# Sensor.net
KiCad netlist of a schematic drawn in Altium Designer
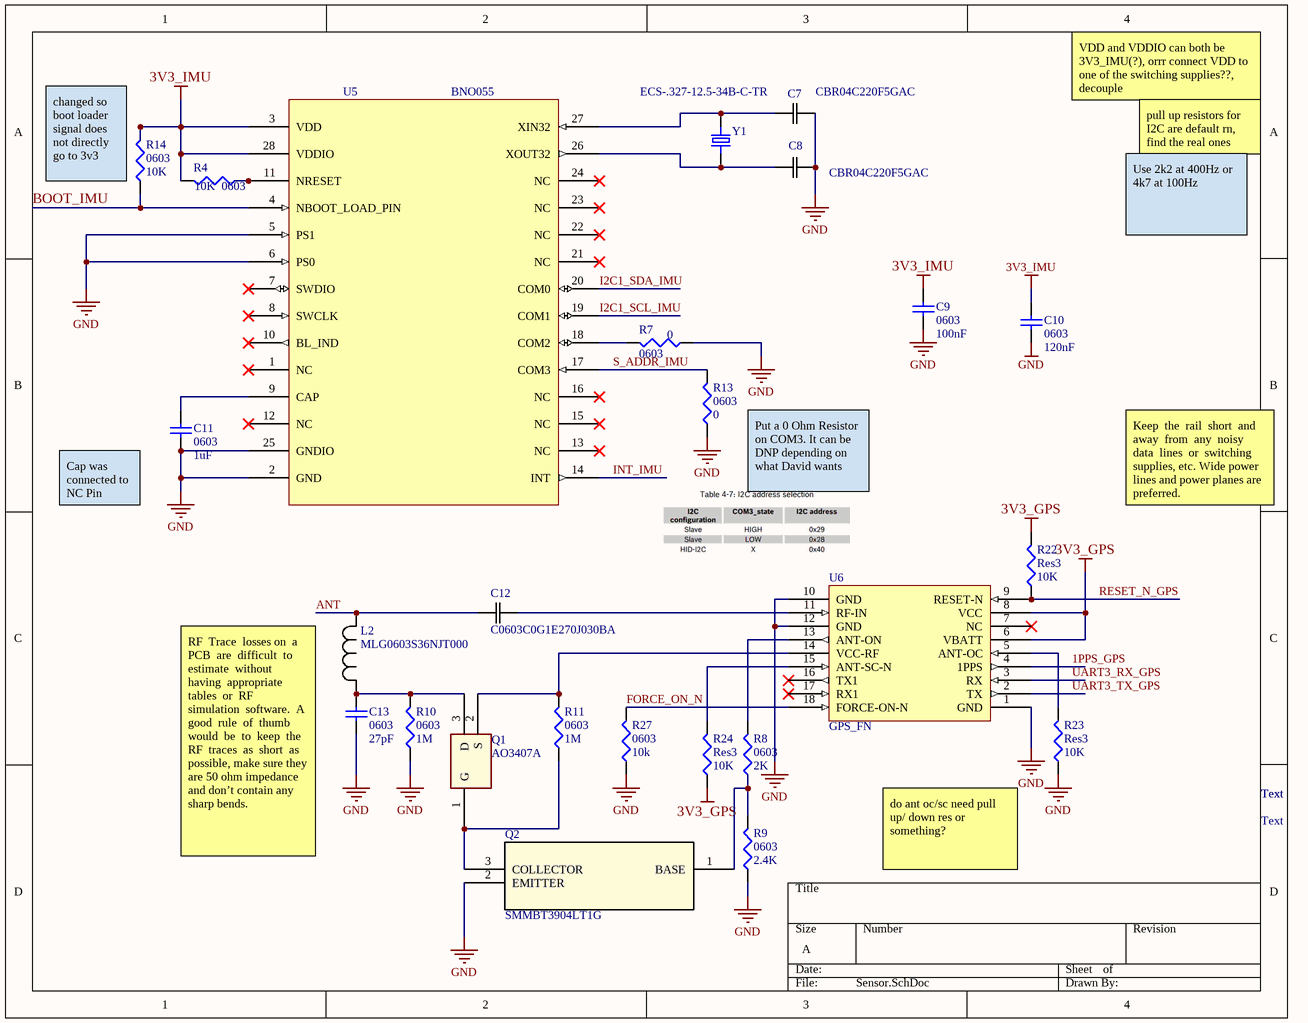
[diagram p0: Sensor.SchDoc]

(export (version "E")
  (design (tool "Eeschema 10.0.6"))
  (components
    (comp (ref "C7")
      (value "CBR04C220F5GAC")
      (footprint "swarm_crawler_pcb:CAPC10555_55N_KEM")
      (description "No Description Available")
      (fields (field (name "COPYRIGHT") "Copyright (C) 2023 Ultra Librarian. All rights reserved."))
      (libsource (lib "swarm_crawler_sch") (part "CBR04C220F5GAC"))
    )
    (comp (ref "C8")
      (value "CBR04C220F5GAC")
      (footprint "swarm_crawler_pcb:CAPC10555_55N_KEM")
      (description "No Description Available")
      (fields (field (name "COPYRIGHT") "Copyright (C) 2023 Ultra Librarian. All rights reserved."))
      (libsource (lib "swarm_crawler_sch") (part "CBR04C220F5GAC"))
    )
    (comp (ref "C9")
      (value "0603")
      (footprint "1608[0603]")
      (description "Capacitor (Semiconductor SIM Model)")
      (fields (field (name "ALTIUM_VALUE") "100nF") (field (name "PUBLISHER") "Altium Limited"))
      (libsource (lib "Miscellaneous Devices") (part "Cap Semi"))
    )
    (comp (ref "C10")
      (value "0603")
      (footprint "1608[0603]")
      (description "Capacitor (Semiconductor SIM Model)")
      (fields (field (name "ALTIUM_VALUE") "120nF") (field (name "PUBLISHER") "Altium Limited"))
      (libsource (lib "Miscellaneous Devices") (part "Cap Semi"))
    )
    (comp (ref "C11")
      (value "0603")
      (footprint "1608[0603]")
      (description "Capacitor (Semiconductor SIM Model)")
      (fields (field (name "ALTIUM_VALUE") "1uF") (field (name "PUBLISHER") "Altium Limited"))
      (libsource (lib "Miscellaneous Devices") (part "Cap Semi"))
    )
    (comp (ref "C12")
      (value "C0603C0G1E270J030BA")
      (footprint "swarm_crawler_pcb:CAP_0603_TDK")
      (description "No Description Available")
      (fields (field (name "COPYRIGHT") "Copyright (C) 2023 Ultra Librarian. All rights reserved."))
      (libsource (lib "swarm_crawler_sch") (part "C0603C0G1E270J030BA"))
    )
    (comp (ref "C13")
      (value "0603")
      (footprint "1608[0603]")
      (description "Capacitor (Semiconductor SIM Model)")
      (fields (field (name "ALTIUM_VALUE") "27pF") (field (name "PUBLISHER") "Altium Limited"))
      (libsource (lib "Miscellaneous Devices") (part "Cap Semi"))
    )
    (comp (ref "L2")
      (value "MLG0603S36NJT000")
      (footprint "swarm_crawler_pcb:IND_0603_TDK")
      (description "No Description Available")
      (fields (field (name "COPYRIGHT") "Copyright (C) 2023 Ultra Librarian. All rights reserved."))
      (libsource (lib "swarm_crawler_sch") (part "MLG0603S36NJT000"))
    )
    (comp (ref "Q1")
      (value "AO3407A")
      (footprint "swarm_crawler_pcb:SOT-23-3L_AOS")
      (description "No Description Available")
      (fields (field (name "COPYRIGHT") "Copyright (C) 2023 Ultra Librarian. All rights reserved."))
      (libsource (lib "swarm_crawler_sch") (part "AO3407A"))
    )
    (comp (ref "Q2")
      (value "SMMBT3904LT1G")
      (footprint "swarm_crawler_pcb:SOT-23-3_1P4X3P040_ONS")
      (description "No Description Available")
      (fields (field (name "COPYRIGHT") "Copyright (C) 2023 Ultra Librarian. All rights reserved."))
      (libsource (lib "swarm_crawler_sch") (part "SMMBT3904LT1G"))
    )
    (comp (ref "R4")
      (value "0603")
      (footprint "J1-0603")
      (description "Resistor")
      (fields (field (name "ALTIUM_VALUE") "10K") (field (name "PUBLISHER") "Altium Limited"))
      (libsource (lib "Miscellaneous Devices") (part "Res3"))
    )
    (comp (ref "R7")
      (value "0603")
      (footprint "J1-0603")
      (description "Resistor")
      (fields (field (name "ALTIUM_VALUE") "0") (field (name "PUBLISHER") "Altium Limited"))
      (libsource (lib "Miscellaneous Devices") (part "Res3"))
    )
    (comp (ref "R8")
      (value "0603")
      (footprint "J1-0603")
      (description "Resistor")
      (fields (field (name "ALTIUM_VALUE") "2K") (field (name "PUBLISHER") "Altium Limited"))
      (libsource (lib "Miscellaneous Devices") (part "Res3"))
    )
    (comp (ref "R9")
      (value "0603")
      (footprint "J1-0603")
      (description "Resistor")
      (fields (field (name "ALTIUM_VALUE") "2.4K") (field (name "PUBLISHER") "Altium Limited"))
      (libsource (lib "Miscellaneous Devices") (part "Res3"))
    )
    (comp (ref "R10")
      (value "0603")
      (footprint "J1-0603")
      (description "Resistor")
      (fields (field (name "ALTIUM_VALUE") "1M") (field (name "PUBLISHER") "Altium Limited"))
      (libsource (lib "Miscellaneous Devices") (part "Res3"))
    )
    (comp (ref "R11")
      (value "0603")
      (footprint "J1-0603")
      (description "Resistor")
      (fields (field (name "ALTIUM_VALUE") "1M") (field (name "PUBLISHER") "Altium Limited"))
      (libsource (lib "Miscellaneous Devices") (part "Res3"))
    )
    (comp (ref "R13")
      (value "0603")
      (footprint "J1-0603")
      (description "Resistor")
      (fields (field (name "ALTIUM_VALUE") "0") (field (name "PUBLISHER") "Altium Limited"))
      (libsource (lib "Miscellaneous Devices") (part "Res3"))
    )
    (comp (ref "R14")
      (value "0603")
      (footprint "J1-0603")
      (description "Resistor")
      (fields (field (name "ALTIUM_VALUE") "10K") (field (name "PUBLISHER") "Altium Limited"))
      (libsource (lib "Miscellaneous Devices") (part "Res3"))
    )
    (comp (ref "R22")
      (value "Res3")
      (footprint "J1-0603")
      (description "Resistor")
      (fields (field (name "ALTIUM_VALUE") "10K") (field (name "PUBLISHER") "Altium Limited"))
      (libsource (lib "Miscellaneous Devices") (part "Res3"))
    )
    (comp (ref "R23")
      (value "Res3")
      (footprint "J1-0603")
      (description "Resistor")
      (fields (field (name "ALTIUM_VALUE") "10K") (field (name "PUBLISHER") "Altium Limited"))
      (libsource (lib "Miscellaneous Devices") (part "Res3"))
    )
    (comp (ref "R24")
      (value "Res3")
      (footprint "J1-0603")
      (description "Resistor")
      (fields (field (name "ALTIUM_VALUE") "10K") (field (name "PUBLISHER") "Altium Limited"))
      (libsource (lib "Miscellaneous Devices") (part "Res3"))
    )
    (comp (ref "R27")
      (value "0603")
      (footprint "J1-0603")
      (description "Resistor")
      (fields (field (name "ALTIUM_VALUE") "10k") (field (name "PUBLISHER") "Altium Limited"))
      (libsource (lib "Miscellaneous Devices") (part "Res3"))
    )
    (comp (ref "U5")
      (value "BNO055")
      (footprint "swarm_crawler_pcb:QFN_BNO055_BOS")
      (description "No Description Available")
      (fields (field (name "COPYRIGHT") "Copyright (C) 2023 Ultra Librarian. All rights reserved."))
      (libsource (lib "swarm_crawler_sch") (part "BNO055"))
    )
    (comp (ref "U6")
      (value "GPS_FN")
      (footprint "swarm_crawler_pcb:SL871")
      (libsource (lib "swarm_crawler_sch") (part "GPS_FN"))
    )
    (comp (ref "Y1")
      (value "ECS-.327-12.5-34B-C-TR")
      (footprint "swarm_crawler_pcb:XTAL_ECS-.327-12.5-34B-C-TR")
      (description "32.768kHz Â±10ppm Crystal 12.5pF 70 kOhms 2-SMD, No Lead")
      (fields (field (name "DIGI-KEY_PART_NUMBER") "XC1968CT-ND") (field (name "MF") "ECS Inc."))
      (libsource (lib "swarm_crawler_sch") (part "ECS-.327-12.5-34B-C-TR"))
    )
  )
  (nets
    (net (code "1") (name "/1PPS_GPS") (class "Default")
      (node (ref "U6") (pin "4") (pinfunction "1PPS_4") (pintype "output"))
    )
    (net (code "2") (name "/ANT") (class "Default")
      (node (ref "C12") (pin "1") (pinfunction "1_1") (pintype "passive"))
      (node (ref "L2") (pin "1") (pinfunction "1_1") (pintype "passive"))
    )
    (net (code "3") (name "/BOOT_IMU") (class "Default")
      (node (ref "R14") (pin "1") (pinfunction "1_1") (pintype "passive"))
      (node (ref "U5") (pin "4") (pinfunction "NBOOT_LOAD_PIN_4") (pintype "input"))
    )
    (net (code "4") (name "/FORCE_ON_N") (class "Default")
      (node (ref "R27") (pin "2") (pinfunction "2_2") (pintype "passive"))
      (node (ref "U6") (pin "18") (pinfunction "FORCE-ON-N_18") (pintype "input"))
    )
    (net (code "5") (name "/I2C1_SCL_IMU") (class "Default")
      (node (ref "U5") (pin "19") (pinfunction "COM1_19") (pintype "bidirectional"))
    )
    (net (code "6") (name "/I2C1_SDA_IMU") (class "Default")
      (node (ref "U5") (pin "20") (pinfunction "COM0_20") (pintype "bidirectional"))
    )
    (net (code "7") (name "/INT_IMU") (class "Default")
      (node (ref "U5") (pin "14") (pinfunction "INT_14") (pintype "output"))
    )
    (net (code "8") (name "/RESET_N_GPS") (class "Default")
      (node (ref "R22") (pin "1") (pinfunction "1_1") (pintype "passive"))
      (node (ref "U6") (pin "9") (pinfunction "RESET-N_9") (pintype "input"))
    )
    (net (code "9") (name "/S_ADDR_IMU") (class "Default")
      (node (ref "R13") (pin "2") (pinfunction "2_2") (pintype "passive"))
      (node (ref "U5") (pin "17") (pinfunction "COM3_17") (pintype "input"))
    )
    (net (code "10") (name "/UART3_RX_GPS") (class "Default")
      (node (ref "U6") (pin "3") (pinfunction "RX_3") (pintype "input"))
    )
    (net (code "11") (name "/UART3_TX_GPS") (class "Default")
      (node (ref "U6") (pin "2") (pinfunction "TX_2") (pintype "output"))
    )
    (net (code "12") (name "3V3_GPS") (class "Default")
      (node (ref "R22") (pin "2") (pinfunction "2_2") (pintype "passive"))
      (node (ref "R24") (pin "1") (pinfunction "1_1") (pintype "passive"))
      (node (ref "U6") (pin "6") (pinfunction "VBATT_6") (pintype "power_in"))
      (node (ref "U6") (pin "8") (pinfunction "VCC_8") (pintype "power_in"))
    )
    (net (code "13") (name "3V3_IMU") (class "Default")
      (node (ref "C10") (pin "2") (pinfunction "2_2") (pintype "passive"))
      (node (ref "C9") (pin "2") (pinfunction "2_2") (pintype "passive"))
      (node (ref "R14") (pin "2") (pinfunction "2_2") (pintype "passive"))
      (node (ref "R4") (pin "2") (pinfunction "2_2") (pintype "passive"))
      (node (ref "U5") (pin "28") (pinfunction "VDDIO_28") (pintype "power_in"))
      (node (ref "U5") (pin "3") (pinfunction "VDD_3") (pintype "power_in"))
    )
    (net (code "14") (name "GND") (class "Default")
      (node (ref "C10") (pin "1") (pinfunction "1_1") (pintype "passive"))
      (node (ref "C11") (pin "1") (pinfunction "1_1") (pintype "passive"))
      (node (ref "C13") (pin "1") (pinfunction "1_1") (pintype "passive"))
      (node (ref "C7") (pin "2") (pinfunction "2_2") (pintype "passive"))
      (node (ref "C8") (pin "2") (pinfunction "2_2") (pintype "passive"))
      (node (ref "C9") (pin "1") (pinfunction "1_1") (pintype "passive"))
      (node (ref "Q2") (pin "2") (pinfunction "EMITTER_2") (pintype "passive"))
      (node (ref "R10") (pin "1") (pinfunction "1_1") (pintype "passive"))
      (node (ref "R13") (pin "1") (pinfunction "1_1") (pintype "passive"))
      (node (ref "R23") (pin "1") (pinfunction "1_1") (pintype "passive"))
      (node (ref "R27") (pin "1") (pinfunction "1_1") (pintype "passive"))
      (node (ref "R7") (pin "1") (pinfunction "1_1") (pintype "passive"))
      (node (ref "R9") (pin "1") (pinfunction "1_1") (pintype "passive"))
      (node (ref "U5") (pin "2") (pinfunction "GND_2") (pintype "passive"))
      (node (ref "U5") (pin "25") (pinfunction "GNDIO_25") (pintype "passive"))
      (node (ref "U5") (pin "5") (pinfunction "PS1_5") (pintype "input"))
      (node (ref "U5") (pin "6") (pinfunction "PS0_6") (pintype "input"))
      (node (ref "U6") (pin "1") (pinfunction "GND_1") (pintype "power_in"))
      (node (ref "U6") (pin "10") (pinfunction "GND_10") (pintype "power_in"))
      (node (ref "U6") (pin "12") (pinfunction "GND_12") (pintype "power_in"))
    )
    (net (code "15") (name "Net-(Q1-D)") (class "Default")
      (node (ref "C13") (pin "2") (pinfunction "2_2") (pintype "passive"))
      (node (ref "L2") (pin "2") (pinfunction "2_2") (pintype "passive"))
      (node (ref "Q1") (pin "3") (pinfunction "D_3") (pintype "passive"))
      (node (ref "R10") (pin "2") (pinfunction "2_2") (pintype "passive"))
    )
    (net (code "16") (name "Net-(Q1-G)") (class "Default")
      (node (ref "Q1") (pin "1") (pinfunction "G_1") (pintype "passive"))
      (node (ref "Q2") (pin "3") (pinfunction "COLLECTOR_3") (pintype "passive"))
      (node (ref "R11") (pin "1") (pinfunction "1_1") (pintype "passive"))
    )
    (net (code "17") (name "Net-(Q1-S)") (class "Default")
      (node (ref "Q1") (pin "2") (pinfunction "S_2") (pintype "passive"))
      (node (ref "R11") (pin "2") (pinfunction "2_2") (pintype "passive"))
      (node (ref "U6") (pin "14") (pinfunction "VCC-RF_14") (pintype "power_in"))
    )
    (net (code "18") (name "Net-(Q2-BASE)") (class "Default")
      (node (ref "Q2") (pin "1") (pinfunction "BASE_1") (pintype "passive"))
      (node (ref "R8") (pin "1") (pinfunction "1_1") (pintype "passive"))
      (node (ref "R9") (pin "2") (pinfunction "2_2") (pintype "passive"))
    )
    (net (code "19") (name "Net-(U5-CAP)") (class "Default")
      (node (ref "C11") (pin "2") (pinfunction "2_2") (pintype "passive"))
      (node (ref "U5") (pin "9") (pinfunction "CAP_9") (pintype "passive"))
    )
    (net (code "20") (name "Net-(U5-COM2)") (class "Default")
      (node (ref "R7") (pin "2") (pinfunction "2_2") (pintype "passive"))
      (node (ref "U5") (pin "18") (pinfunction "COM2_18") (pintype "bidirectional"))
    )
    (net (code "21") (name "Net-(U5-NRESET)") (class "Default")
      (node (ref "R4") (pin "1") (pinfunction "1_1") (pintype "passive"))
      (node (ref "U5") (pin "11") (pinfunction "NRESET_11") (pintype "passive"))
    )
    (net (code "22") (name "Net-(U5-XIN32)") (class "Default")
      (node (ref "C7") (pin "1") (pinfunction "1_1") (pintype "passive"))
      (node (ref "U5") (pin "27") (pinfunction "XIN32_27") (pintype "input"))
      (node (ref "Y1") (pin "2") (pinfunction "2_2") (pintype "passive"))
    )
    (net (code "23") (name "Net-(U5-XOUT32)") (class "Default")
      (node (ref "C8") (pin "1") (pinfunction "1_1") (pintype "passive"))
      (node (ref "U5") (pin "26") (pinfunction "XOUT32_26") (pintype "output"))
      (node (ref "Y1") (pin "1") (pinfunction "1_1") (pintype "passive"))
    )
    (net (code "24") (name "Net-(U6-ANT-OC)") (class "Default")
      (node (ref "R23") (pin "2") (pinfunction "2_2") (pintype "passive"))
      (node (ref "U6") (pin "5") (pinfunction "ANT-OC_5") (pintype "input"))
    )
    (net (code "25") (name "Net-(U6-ANT-ON)") (class "Default")
      (node (ref "R8") (pin "2") (pinfunction "2_2") (pintype "passive"))
      (node (ref "U6") (pin "13") (pinfunction "ANT-ON_13") (pintype "output"))
    )
    (net (code "26") (name "Net-(U6-ANT-SC-N)") (class "Default")
      (node (ref "R24") (pin "2") (pinfunction "2_2") (pintype "passive"))
      (node (ref "U6") (pin "15") (pinfunction "ANT-SC-N_15") (pintype "input"))
    )
    (net (code "27") (name "Net-(U6-RF-IN)") (class "Default")
      (node (ref "C12") (pin "2") (pinfunction "2_2") (pintype "passive"))
      (node (ref "U6") (pin "11") (pinfunction "RF-IN_11") (pintype "input"))
    )
    (net (code "28") (name "unconnected-(U5-BL_IND-Pad10)") (class "Default")
      (node (ref "U5") (pin "10") (pinfunction "BL_IND_10") (pintype "output+no_connect"))
    )
    (net (code "29") (name "unconnected-(U5-NC-Pad1)") (class "Default")
      (node (ref "U5") (pin "1") (pinfunction "NC_1") (pintype "passive+no_connect"))
    )
    (net (code "30") (name "unconnected-(U5-NC-Pad12)") (class "Default")
      (node (ref "U5") (pin "12") (pinfunction "NC_12") (pintype "passive+no_connect"))
    )
    (net (code "31") (name "unconnected-(U5-NC-Pad13)") (class "Default")
      (node (ref "U5") (pin "13") (pinfunction "NC_13") (pintype "passive+no_connect"))
    )
    (net (code "32") (name "unconnected-(U5-NC-Pad15)") (class "Default")
      (node (ref "U5") (pin "15") (pinfunction "NC_15") (pintype "passive+no_connect"))
    )
    (net (code "33") (name "unconnected-(U5-NC-Pad16)") (class "Default")
      (node (ref "U5") (pin "16") (pinfunction "NC_16") (pintype "passive+no_connect"))
    )
    (net (code "34") (name "unconnected-(U5-NC-Pad21)") (class "Default")
      (node (ref "U5") (pin "21") (pinfunction "NC_21") (pintype "passive+no_connect"))
    )
    (net (code "35") (name "unconnected-(U5-NC-Pad22)") (class "Default")
      (node (ref "U5") (pin "22") (pinfunction "NC_22") (pintype "passive+no_connect"))
    )
    (net (code "36") (name "unconnected-(U5-NC-Pad23)") (class "Default")
      (node (ref "U5") (pin "23") (pinfunction "NC_23") (pintype "passive+no_connect"))
    )
    (net (code "37") (name "unconnected-(U5-NC-Pad24)") (class "Default")
      (node (ref "U5") (pin "24") (pinfunction "NC_24") (pintype "passive+no_connect"))
    )
    (net (code "38") (name "unconnected-(U5-SWCLK-Pad8)") (class "Default")
      (node (ref "U5") (pin "8") (pinfunction "SWCLK_8") (pintype "input+no_connect"))
    )
    (net (code "39") (name "unconnected-(U5-SWDIO-Pad7)") (class "Default")
      (node (ref "U5") (pin "7") (pinfunction "SWDIO_7") (pintype "bidirectional+no_connect"))
    )
    (net (code "40") (name "unconnected-(U6-NC-Pad7)") (class "Default")
      (node (ref "U6") (pin "7") (pinfunction "NC_7") (pintype "passive+no_connect"))
    )
    (net (code "41") (name "unconnected-(U6-RX1-Pad17)") (class "Default")
      (node (ref "U6") (pin "17") (pinfunction "RX1_17") (pintype "input+no_connect"))
    )
    (net (code "42") (name "unconnected-(U6-TX1-Pad16)") (class "Default")
      (node (ref "U6") (pin "16") (pinfunction "TX1_16") (pintype "output+no_connect"))
    )
  )
)
